# HeaterFlowRegulator_2021-05-24.net
KiCad netlist of a schematic drawn in EasyEDA
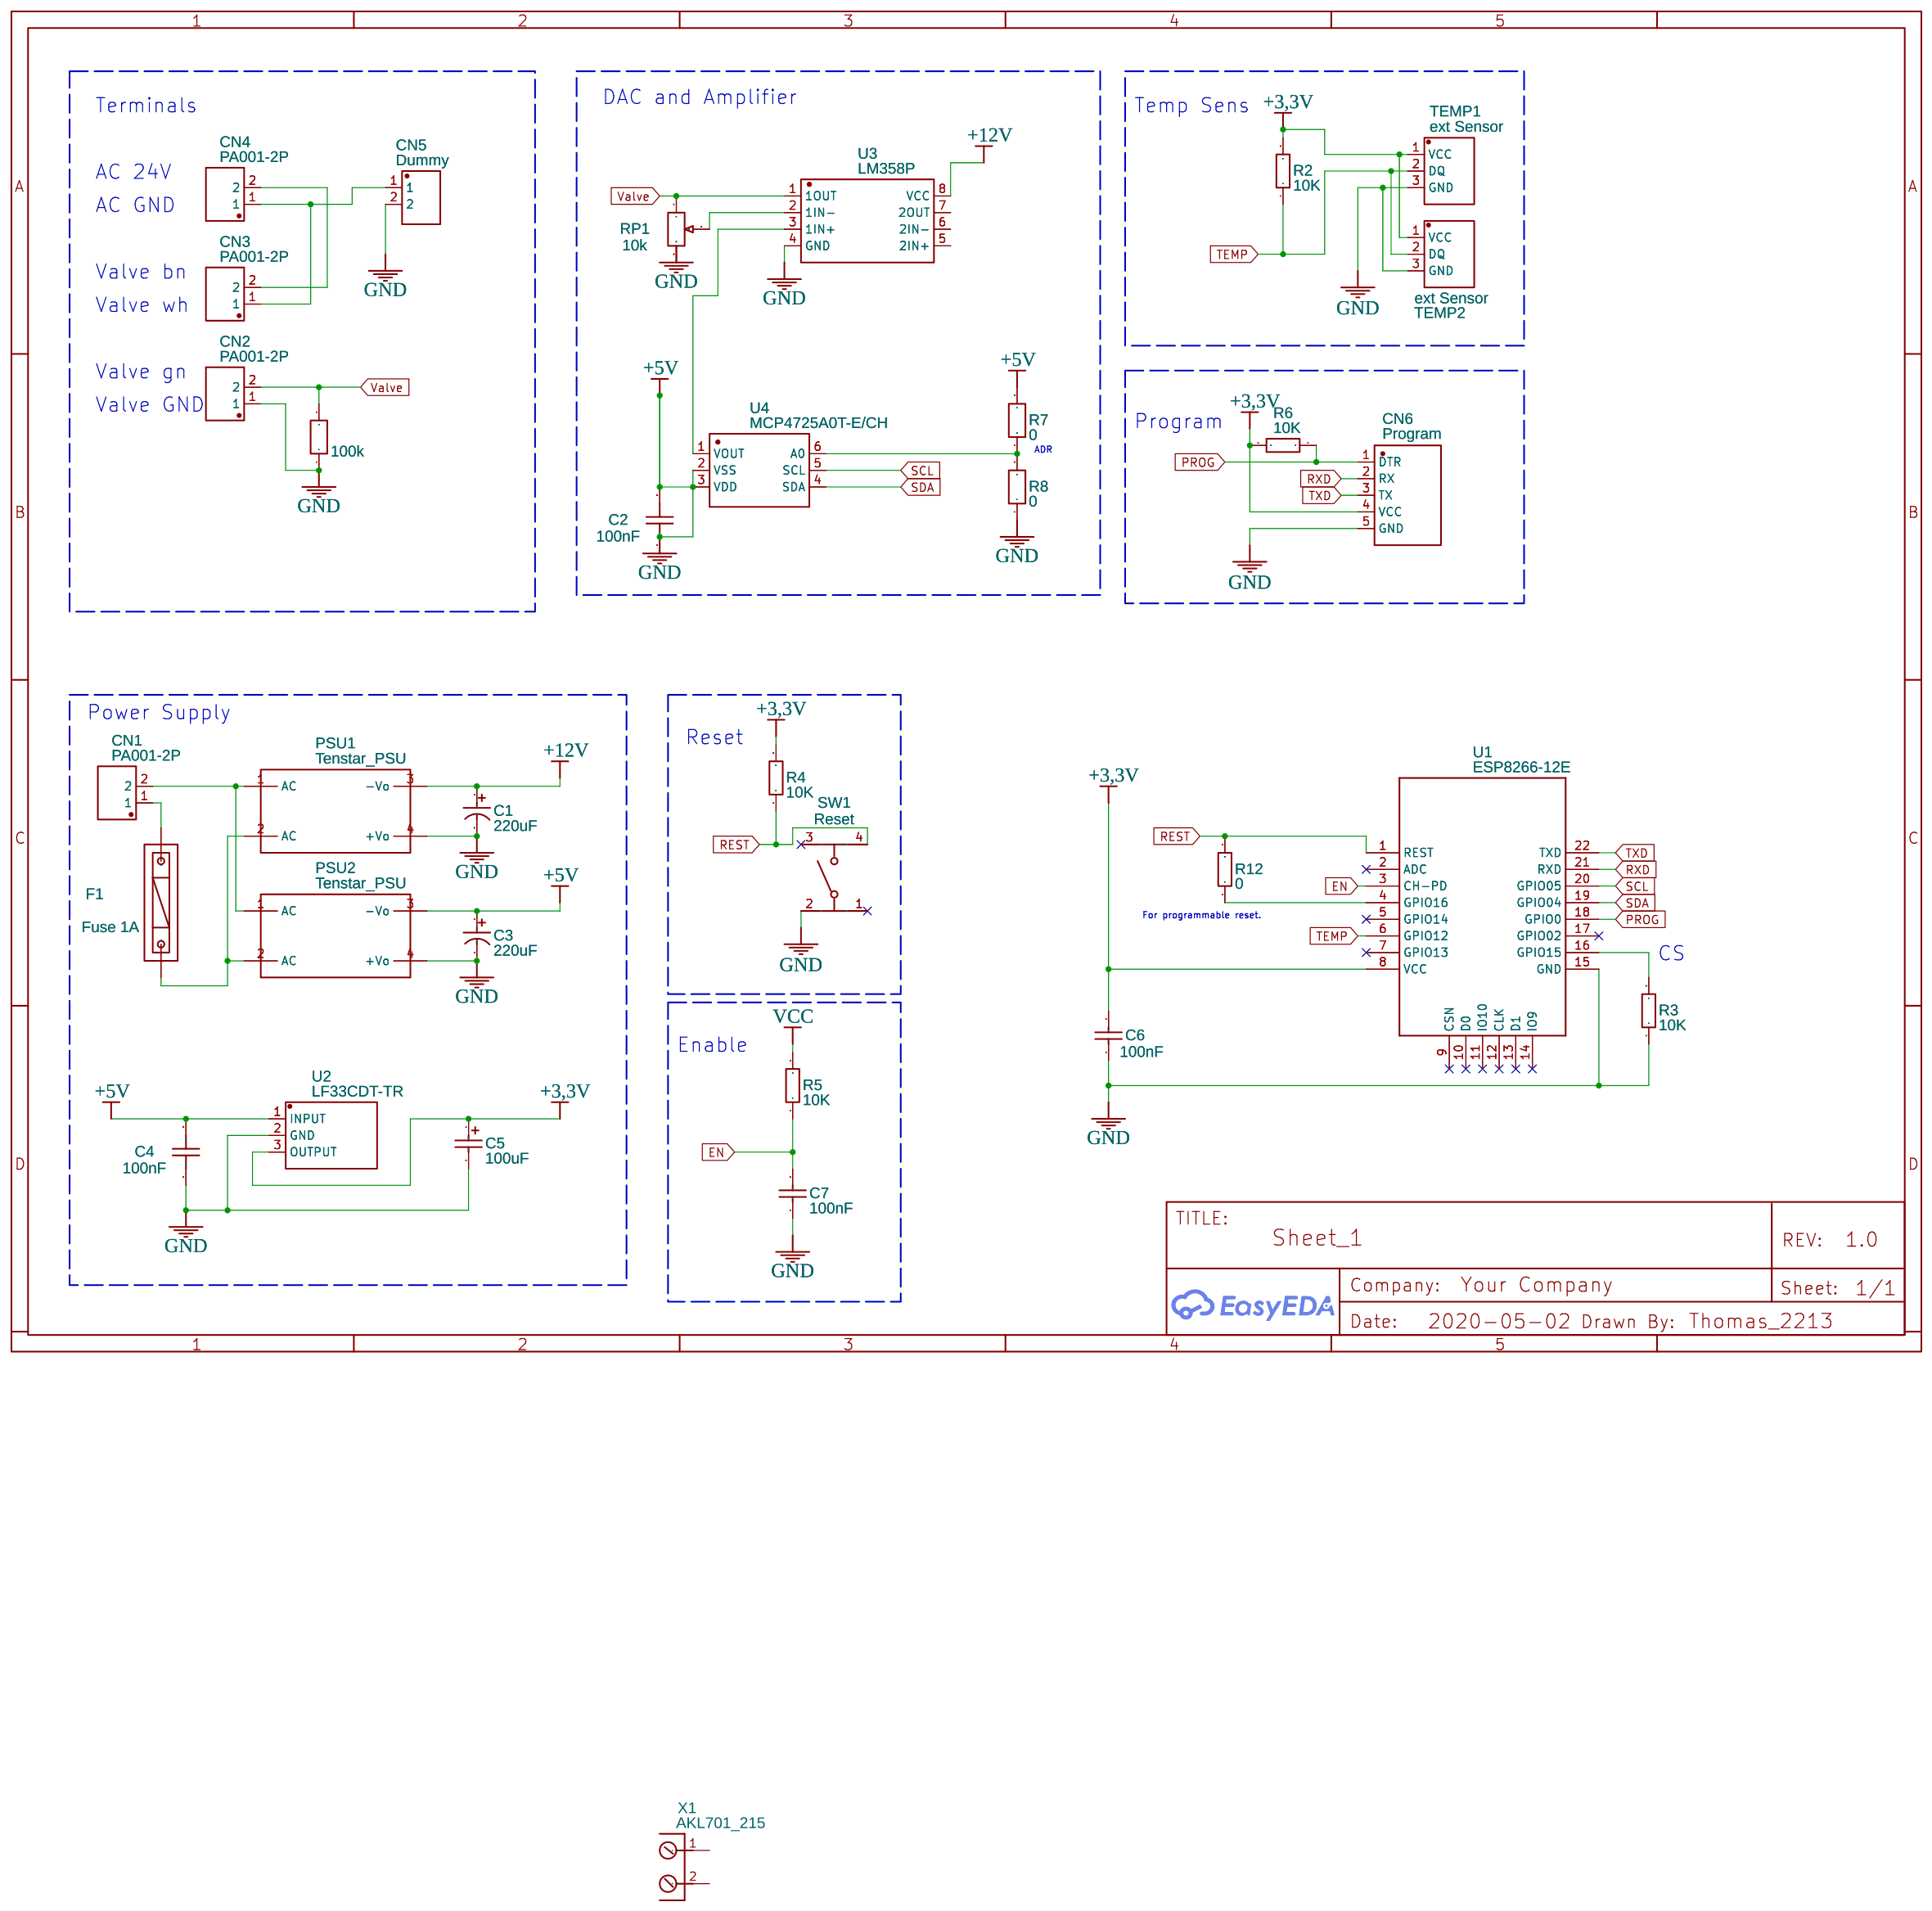
[diagram p0: schematic sheet]

(export (version "E")
  (design (tool "Eeschema 10.0.6"))
  (components
    (comp (ref "C1")
      (value "220uF")
      (fields (field (name "BOM_Manufacturer Part") "220uf/35V") (field (name "BOM_Supplier Part") "C2063"))
      (libsource (lib "") (part "220uf/35V"))
    )
    (comp (ref "C2")
      (value "100nF")
      (fields
        (field (name "BOM_Manufacturer Part") "CL10B104KC8NNNC")
        (field (name "BOM_Supplier Part") "C15725")
      )
      (libsource (lib "") (part "CL10B104KC8NNNC"))
    )
    (comp (ref "C3")
      (value "220uF")
      (fields (field (name "BOM_Manufacturer Part") "220uf/35V") (field (name "BOM_Supplier Part") "C2063"))
      (libsource (lib "") (part "220uf/35V"))
    )
    (comp (ref "C4")
      (value "100nF")
      (fields
        (field (name "BOM_Manufacturer Part") "CL10B104KC8NNNC")
        (field (name "BOM_Supplier Part") "C15725")
      )
      (libsource (lib "") (part "CL10B104KC8NNNC"))
    )
    (comp (ref "C5")
      (value "100uF")
      (fields
        (field (name "BOM_Manufacturer Part") "TAJB107K006RNJ")
        (field (name "BOM_Supplier Part") "C16133")
      )
      (libsource (lib "") (part "TAJB107K006RNJ"))
    )
    (comp (ref "C6")
      (value "100nF")
      (fields
        (field (name "BOM_Manufacturer Part") "CL10B104KC8NNNC")
        (field (name "BOM_Supplier Part") "C15725")
      )
      (libsource (lib "") (part "CL10B104JB8NNNC"))
    )
    (comp (ref "C7")
      (value "100nF")
      (fields
        (field (name "BOM_Manufacturer Part") "CL10B104JB8NNNC")
        (field (name "BOM_Supplier Part") "C24452")
      )
      (libsource (lib "") (part "CL10B104JB8NNNC"))
    )
    (comp (ref "CN1")
      (value "PA001-2P")
      (fields (field (name "BOM_Supplier Part") "C128027"))
      (libsource (lib "") (part "PA001-2P"))
    )
    (comp (ref "CN2")
      (value "PA001-2P")
      (fields (field (name "BOM_Supplier Part") "C128027"))
      (libsource (lib "") (part "PA001-2P"))
    )
    (comp (ref "CN3")
      (value "PA001-2P")
      (fields (field (name "BOM_Supplier Part") "C128027"))
      (libsource (lib "") (part "PA001-2P"))
    )
    (comp (ref "CN4")
      (value "PA001-2P")
      (fields (field (name "BOM_Supplier Part") "C128027"))
      (libsource (lib "") (part "PA001-2P"))
    )
    (comp (ref "CN5")
      (value "Dummy")
      (fields (field (name "BOM_Manufacturer Part") "PA001-2P") (field (name "BOM_Supplier Part") "C128027"))
      (libsource (lib "") (part "PA001-2P_1"))
    )
    (comp (ref "CN6")
      (value "Program")
      (fields (field (name "BOM_Supplier Part") "C161872"))
      (libsource (lib "") (part "B5B-XH-AM (LF)(SN)"))
    )
    (comp (ref "F1")
      (value "Fuse 1A")
      (fields
        (field (name "BOM_Manufacturer Part") "Fuse transparent seat")
        (field (name "BOM_Supplier Part") "C58066")
      )
      (libsource (lib "") (part "Fuse transparent seat"))
    )
    (comp (ref "PSU1")
      (value "Tenstar_PSU")
      (fields
        (field (name "BOM_Manufacturer Part") "Tenstar Robot")
        (field (name "BOM_Supplier Part") "TSP-05")
      )
      (libsource (lib "") (part "Tenstar_PSU"))
    )
    (comp (ref "PSU2")
      (value "Tenstar_PSU")
      (fields
        (field (name "BOM_Manufacturer Part") "Tenstar Robot")
        (field (name "BOM_Supplier Part") "TSP-05")
      )
      (libsource (lib "") (part "Tenstar_PSU"))
    )
    (comp (ref "R1") (value "100k") (libsource (lib "") (part "R_0201_EU")))
    (comp (ref "R2")
      (value "10K")
      (fields
        (field (name "BOM_Manufacturer Part") "TC0325B1002T5E")
        (field (name "BOM_Supplier Part") "C39050")
      )
      (libsource (lib "") (part "TC0310B1002T5E"))
    )
    (comp (ref "R3")
      (value "10K")
      (fields
        (field (name "BOM_Manufacturer Part") "TC0325B1002T5E")
        (field (name "BOM_Supplier Part") "C39050")
      )
      (libsource (lib "") (part "TC0310B1002T5E"))
    )
    (comp (ref "R4")
      (value "10K")
      (fields
        (field (name "BOM_Manufacturer Part") "TC0310B1002T5E")
        (field (name "BOM_Supplier Part") "C190321")
      )
      (libsource (lib "") (part "TC0310B1002T5E"))
    )
    (comp (ref "R5")
      (value "10K")
      (fields
        (field (name "BOM_Manufacturer Part") "TC0310B1002T5E")
        (field (name "BOM_Supplier Part") "C190321")
      )
      (libsource (lib "") (part "TC0310B1002T5E"))
    )
    (comp (ref "R6")
      (value "10K")
      (fields
        (field (name "BOM_Manufacturer Part") "TC0310B1002T5E")
        (field (name "BOM_Supplier Part") "C190321")
      )
      (libsource (lib "") (part "TC0310B1002T5E_1"))
    )
    (comp (ref "R7") (value "0") (libsource (lib "") (part "R_0603_EU")))
    (comp (ref "R8") (value "0") (libsource (lib "") (part "R_0603_EU")))
    (comp (ref "R12")
      (value "0")
      (fields
        (field (name "BOM_Manufacturer Part") "0603WAJ0000T5E")
        (field (name "BOM_Supplier Part") "C15402")
      )
      (libsource (lib "") (part "0603WAJ0000T5E"))
    )
    (comp (ref "RP1") (value "10k") (libsource (lib "") (part "R_3386P_EU")))
    (comp (ref "SW1")
      (value "Reset")
      (fields
        (field (name "BOM_Manufacturer Part") "TL3301TF160QG/D310794")
        (field (name "BOM_Supplier Part") "C273532")
      )
      (libsource (lib "") (part "TL3301TF160QG/D310794"))
    )
    (comp (ref "TEMP1")
      (value "ext Sensor")
      (fields
        (field (name "BOM_Manufacturer Part") "B3B-XH-AM-(LF)(SN)")
        (field (name "BOM_Supplier Part") "C161870")
      )
      (libsource (lib "") (part "B3B-XH-AM-(LF)(SN)"))
    )
    (comp (ref "TEMP2")
      (value "ext Sensor")
      (fields
        (field (name "BOM_Manufacturer Part") "B3B-XH-AM-(LF)(SN)")
        (field (name "BOM_Supplier Part") "C161870")
      )
      (libsource (lib "") (part "B3B-XH-AM-(LF)(SN)"))
    )
    (comp (ref "U1")
      (value "ESP8266-12E")
      (fields
        (field (name "BOM_Manufacturer Part") "ESP8266-12E/ESP-12E")
        (field (name "BOM_Supplier Part") "317060015")
      )
      (libsource (lib "") (part "Unknown_885_-250"))
    )
    (comp (ref "U2")
      (value "LF33CDT-TR")
      (fields (field (name "BOM_Supplier Part") "C222179"))
      (libsource (lib "") (part "LF33CDT-TR"))
    )
    (comp (ref "U3")
      (value "LM358P")
      (fields (field (name "BOM_Supplier Part") "C5213"))
      (libsource (lib "") (part "LM358P"))
    )
    (comp (ref "U4")
      (value "MCP4725A0T-E/CH")
      (fields (field (name "BOM_Supplier Part") "C144198"))
      (libsource (lib "") (part "MCP4725A0T-E/CH"))
    )
    (comp (ref "X1") (value "AKL701_215") (libsource (lib "") (part "AKL701_215")))
  )
  (nets
    (net (code "1") (name "+3,3V") (class "Default")
      (node (ref "C5") (pin "1") (pinfunction "1_1") (pintype "input"))
      (node (ref "C6") (pin "2") (pinfunction "2_2") (pintype "input"))
      (node (ref "CN6") (pin "4") (pinfunction "VCC_4") (pintype "unspecified"))
      (node (ref "R2") (pin "2") (pinfunction "2_2") (pintype "unspecified"))
      (node (ref "R4") (pin "2") (pinfunction "2_2") (pintype "unspecified"))
      (node (ref "R6") (pin "2") (pinfunction "2_2") (pintype "unspecified"))
      (node (ref "TEMP1") (pin "1") (pinfunction "VCC_1") (pintype "unspecified"))
      (node (ref "TEMP2") (pin "1") (pinfunction "VCC_1") (pintype "unspecified"))
      (node (ref "U1") (pin "8") (pinfunction "VCC_8") (pintype "unspecified"))
      (node (ref "U2") (pin "3") (pinfunction "OUTPUT_3") (pintype "unspecified"))
    )
    (net (code "2") (name "+5V") (class "Default")
      (node (ref "C1") (pin "2") (pinfunction "2_2") (pintype "input"))
      (node (ref "C2") (pin "1") (pinfunction "1_1") (pintype "unspecified"))
      (node (ref "C2") (pin "2") (pinfunction "2_2") (pintype "unspecified"))
      (node (ref "C3") (pin "1") (pinfunction "1_1") (pintype "input"))
      (node (ref "C3") (pin "2") (pinfunction "2_2") (pintype "input"))
      (node (ref "C4") (pin "1") (pinfunction "1_1") (pintype "unspecified"))
      (node (ref "C4") (pin "2") (pinfunction "2_2") (pintype "unspecified"))
      (node (ref "C5") (pin "2") (pinfunction "2_2") (pintype "input"))
      (node (ref "C6") (pin "1") (pinfunction "1_1") (pintype "input"))
      (node (ref "C7") (pin "1") (pinfunction "1_1") (pintype "input"))
      (node (ref "CN2") (pin "1") (pinfunction "1_1") (pintype "unspecified"))
      (node (ref "CN5") (pin "2") (pinfunction "2_2") (pintype "unspecified"))
      (node (ref "CN6") (pin "5") (pinfunction "GND_5") (pintype "unspecified"))
      (node (ref "PSU1") (pin "4") (pinfunction "+Vo_4") (pintype "unspecified"))
      (node (ref "PSU2") (pin "3") (pinfunction "-Vo_3") (pintype "unspecified"))
      (node (ref "PSU2") (pin "4") (pinfunction "+Vo_4") (pintype "unspecified"))
      (node (ref "R1") (pin "1") (pinfunction "1_1") (pintype "unspecified"))
      (node (ref "R3") (pin "1") (pinfunction "1_1") (pintype "unspecified"))
      (node (ref "R7") (pin "2") (pinfunction "2_2") (pintype "unspecified"))
      (node (ref "R8") (pin "1") (pinfunction "1_1") (pintype "unspecified"))
      (node (ref "RP1") (pin "3") (pinfunction "3_3") (pintype "input"))
      (node (ref "SW1") (pin "2") (pinfunction "2_2") (pintype "unspecified"))
      (node (ref "TEMP1") (pin "3") (pinfunction "GND_3") (pintype "unspecified"))
      (node (ref "TEMP2") (pin "3") (pinfunction "GND_3") (pintype "unspecified"))
      (node (ref "U1") (pin "15") (pinfunction "GND_15") (pintype "unspecified"))
      (node (ref "U2") (pin "1") (pinfunction "INPUT_1") (pintype "unspecified"))
      (node (ref "U2") (pin "2") (pinfunction "GND_2") (pintype "unspecified"))
      (node (ref "U3") (pin "4") (pinfunction "GND_4") (pintype "unspecified"))
      (node (ref "U4") (pin "2") (pinfunction "VSS_2") (pintype "unspecified"))
      (node (ref "U4") (pin "3") (pinfunction "VDD_3") (pintype "unspecified"))
    )
    (net (code "3") (name "+12V") (class "Default")
      (node (ref "C1") (pin "1") (pinfunction "1_1") (pintype "input"))
      (node (ref "PSU1") (pin "3") (pinfunction "-Vo_3") (pintype "unspecified"))
      (node (ref "U3") (pin "8") (pinfunction "VCC_8") (pintype "unspecified"))
    )
    (net (code "4") (name "EN") (class "Default")
      (node (ref "C7") (pin "2") (pinfunction "2_2") (pintype "input"))
      (node (ref "R5") (pin "1") (pinfunction "1_1") (pintype "unspecified"))
      (node (ref "U1") (pin "3") (pinfunction "CH-PD_3") (pintype "unspecified"))
    )
    (net (code "5") (name "Net-(CN1-Pad1)") (class "Default")
      (node (ref "CN1") (pin "1") (pinfunction "1_1") (pintype "unspecified"))
      (node (ref "F1") (pin "2") (pinfunction "2_2") (pintype "unspecified"))
    )
    (net (code "6") (name "Net-(CN1-Pad2)") (class "Default")
      (node (ref "CN1") (pin "2") (pinfunction "2_2") (pintype "unspecified"))
      (node (ref "PSU1") (pin "1") (pinfunction "AC_1") (pintype "unspecified"))
      (node (ref "PSU2") (pin "1") (pinfunction "AC_1") (pintype "unspecified"))
    )
    (net (code "7") (name "Net-(CN3-Pad1)") (class "Default")
      (node (ref "CN3") (pin "1") (pinfunction "1_1") (pintype "unspecified"))
      (node (ref "CN4") (pin "1") (pinfunction "1_1") (pintype "unspecified"))
      (node (ref "CN5") (pin "1") (pinfunction "1_1") (pintype "unspecified"))
    )
    (net (code "8") (name "Net-(CN3-Pad2)") (class "Default")
      (node (ref "CN3") (pin "2") (pinfunction "2_2") (pintype "unspecified"))
      (node (ref "CN4") (pin "2") (pinfunction "2_2") (pintype "unspecified"))
    )
    (net (code "9") (name "Net-(F1-Pad1)") (class "Default")
      (node (ref "F1") (pin "1") (pinfunction "1_1") (pintype "unspecified"))
      (node (ref "PSU1") (pin "2") (pinfunction "AC_2") (pintype "unspecified"))
      (node (ref "PSU2") (pin "2") (pinfunction "AC_2") (pintype "unspecified"))
    )
    (net (code "10") (name "Net-(U1-GPIO15)") (class "Default")
      (node (ref "R3") (pin "2") (pinfunction "2_2") (pintype "unspecified"))
      (node (ref "U1") (pin "16") (pinfunction "GPIO15_16") (pintype "unspecified"))
    )
    (net (code "11") (name "Net-(U1-GPIO16)") (class "Default")
      (node (ref "R12") (pin "1") (pinfunction "1_1") (pintype "input"))
      (node (ref "U1") (pin "4") (pinfunction "GPIO16_4") (pintype "unspecified"))
    )
    (net (code "12") (name "Net-(U3-1IN+)") (class "Default")
      (node (ref "U3") (pin "3") (pinfunction "1IN+_3") (pintype "unspecified"))
      (node (ref "U4") (pin "1") (pinfunction "VOUT_1") (pintype "unspecified"))
    )
    (net (code "13") (name "Net-(U3-1IN-)") (class "Default")
      (node (ref "RP1") (pin "2") (pinfunction "2_2") (pintype "input"))
      (node (ref "U3") (pin "2") (pinfunction "1IN-_2") (pintype "unspecified"))
    )
    (net (code "14") (name "Net-(U4-A0)") (class "Default")
      (node (ref "R7") (pin "1") (pinfunction "1_1") (pintype "unspecified"))
      (node (ref "R8") (pin "2") (pinfunction "2_2") (pintype "unspecified"))
      (node (ref "U4") (pin "6") (pinfunction "A0_6") (pintype "unspecified"))
    )
    (net (code "15") (name "PROG") (class "Default")
      (node (ref "CN6") (pin "1") (pinfunction "DTR_1") (pintype "unspecified"))
      (node (ref "R6") (pin "1") (pinfunction "1_1") (pintype "unspecified"))
      (node (ref "U1") (pin "18") (pinfunction "GPIO0_18") (pintype "unspecified"))
    )
    (net (code "16") (name "REST") (class "Default")
      (node (ref "R12") (pin "2") (pinfunction "2_2") (pintype "input"))
      (node (ref "R4") (pin "1") (pinfunction "1_1") (pintype "unspecified"))
      (node (ref "SW1") (pin "4") (pinfunction "4_4") (pintype "unspecified"))
      (node (ref "U1") (pin "1") (pinfunction "REST_1") (pintype "unspecified"))
    )
    (net (code "17") (name "RXD") (class "Default")
      (node (ref "CN6") (pin "2") (pinfunction "RX_2") (pintype "unspecified"))
      (node (ref "U1") (pin "21") (pinfunction "RXD_21") (pintype "unspecified"))
    )
    (net (code "18") (name "SCL") (class "Default")
      (node (ref "U1") (pin "20") (pinfunction "GPIO05_20") (pintype "unspecified"))
      (node (ref "U4") (pin "5") (pinfunction "SCL_5") (pintype "unspecified"))
    )
    (net (code "19") (name "SDA") (class "Default")
      (node (ref "U1") (pin "19") (pinfunction "GPIO04_19") (pintype "unspecified"))
      (node (ref "U4") (pin "4") (pinfunction "SDA_4") (pintype "unspecified"))
    )
    (net (code "20") (name "TEMP") (class "Default")
      (node (ref "R2") (pin "1") (pinfunction "1_1") (pintype "unspecified"))
      (node (ref "TEMP1") (pin "2") (pinfunction "DQ_2") (pintype "unspecified"))
      (node (ref "TEMP2") (pin "2") (pinfunction "DQ_2") (pintype "unspecified"))
      (node (ref "U1") (pin "6") (pinfunction "GPIO12_6") (pintype "unspecified"))
    )
    (net (code "21") (name "TXD") (class "Default")
      (node (ref "CN6") (pin "3") (pinfunction "TX_3") (pintype "unspecified"))
      (node (ref "U1") (pin "22") (pinfunction "TXD_22") (pintype "unspecified"))
    )
    (net (code "22") (name "VCC") (class "Default")
      (node (ref "R5") (pin "2") (pinfunction "2_2") (pintype "unspecified"))
    )
    (net (code "23") (name "Valve") (class "Default")
      (node (ref "CN2") (pin "2") (pinfunction "2_2") (pintype "unspecified"))
      (node (ref "R1") (pin "2") (pinfunction "2_2") (pintype "unspecified"))
      (node (ref "RP1") (pin "1") (pinfunction "1_1") (pintype "input"))
      (node (ref "U3") (pin "1") (pinfunction "1OUT_1") (pintype "unspecified"))
    )
    (net (code "24") (name "unconnected-(SW1-Pad1)") (class "Default")
      (node (ref "SW1") (pin "1") (pinfunction "1_1") (pintype "unspecified+no_connect"))
    )
    (net (code "25") (name "unconnected-(SW1-Pad3)") (class "Default")
      (node (ref "SW1") (pin "3") (pinfunction "3_3") (pintype "unspecified+no_connect"))
    )
    (net (code "26") (name "unconnected-(U1-ADC-Pad2)") (class "Default")
      (node (ref "U1") (pin "2") (pinfunction "ADC_2") (pintype "unspecified+no_connect"))
    )
    (net (code "27") (name "unconnected-(U1-CLK-Pad12)") (class "Default")
      (node (ref "U1") (pin "12") (pinfunction "CLK_12") (pintype "unspecified+no_connect"))
    )
    (net (code "28") (name "unconnected-(U1-CSN-Pad9)") (class "Default")
      (node (ref "U1") (pin "9") (pinfunction "CSN_9") (pintype "unspecified+no_connect"))
    )
    (net (code "29") (name "unconnected-(U1-D0-Pad10)") (class "Default")
      (node (ref "U1") (pin "10") (pinfunction "D0_10") (pintype "unspecified+no_connect"))
    )
    (net (code "30") (name "unconnected-(U1-D1-Pad13)") (class "Default")
      (node (ref "U1") (pin "13") (pinfunction "D1_13") (pintype "unspecified+no_connect"))
    )
    (net (code "31") (name "unconnected-(U1-GPIO02-Pad17)") (class "Default")
      (node (ref "U1") (pin "17") (pinfunction "GPIO02_17") (pintype "unspecified+no_connect"))
    )
    (net (code "32") (name "unconnected-(U1-GPIO13-Pad7)") (class "Default")
      (node (ref "U1") (pin "7") (pinfunction "GPIO13_7") (pintype "unspecified+no_connect"))
    )
    (net (code "33") (name "unconnected-(U1-GPIO14-Pad5)") (class "Default")
      (node (ref "U1") (pin "5") (pinfunction "GPIO14_5") (pintype "unspecified+no_connect"))
    )
    (net (code "34") (name "unconnected-(U1-IO9-Pad14)") (class "Default")
      (node (ref "U1") (pin "14") (pinfunction "IO9_14") (pintype "unspecified+no_connect"))
    )
    (net (code "35") (name "unconnected-(U1-IO10-Pad11)") (class "Default")
      (node (ref "U1") (pin "11") (pinfunction "IO10_11") (pintype "unspecified+no_connect"))
    )
    (net (code "36") (name "unconnected-(U3-2IN+-Pad5)") (class "Default")
      (node (ref "U3") (pin "5") (pinfunction "2IN+_5") (pintype "unspecified"))
    )
    (net (code "37") (name "unconnected-(U3-2IN--Pad6)") (class "Default")
      (node (ref "U3") (pin "6") (pinfunction "2IN-_6") (pintype "unspecified"))
    )
    (net (code "38") (name "unconnected-(U3-2OUT-Pad7)") (class "Default")
      (node (ref "U3") (pin "7") (pinfunction "2OUT_7") (pintype "unspecified"))
    )
    (net (code "39") (name "unconnected-(X1-Pad1)") (class "Default")
      (node (ref "X1") (pin "1") (pinfunction "1_1") (pintype "unspecified"))
    )
    (net (code "40") (name "unconnected-(X1-Pad2)") (class "Default")
      (node (ref "X1") (pin "2") (pinfunction "2_2") (pintype "unspecified"))
    )
  )
)
